# FOR_A-SOPRADOR.net
KiCad netlist of a schematic drawn in EAGLE
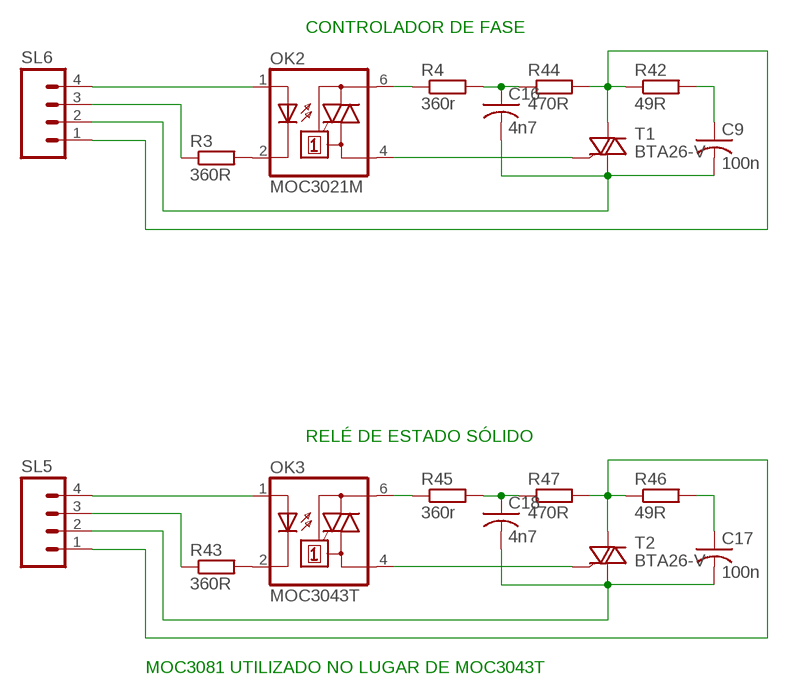
[diagram p0: schematic, sheet 1]

(export (version "E")
  (design (tool "Eeschema 10.0.6"))
  (components
    (comp (ref "C9")
      (value "100n")
      (footprint "eagle-import:C050-035X075")
      (libsource (lib "eagle-import") (part "C-US050-035X075"))
    )
    (comp (ref "C16")
      (value "4n7")
      (footprint "eagle-import:C050-035X075")
      (libsource (lib "eagle-import") (part "C-US050-035X075"))
    )
    (comp (ref "C17")
      (value "100n")
      (footprint "eagle-import:C050-035X075")
      (libsource (lib "eagle-import") (part "C-US050-035X075"))
    )
    (comp (ref "C18")
      (value "4n7")
      (footprint "eagle-import:C050-035X075")
      (libsource (lib "eagle-import") (part "C-US050-035X075"))
    )
    (comp (ref "OK2")
      (value "MOC3021M")
      (footprint "eagle-import:DIL06")
      (fields (field (name "MF") "FAIRCHILD SEMICONDUCTOR") (field (name "MPN") "MOC3021-M"))
      (libsource (lib "eagle-import") (part "MOC30M21"))
    )
    (comp (ref "OK3")
      (value "MOC3043T")
      (footprint "eagle-import:DIL06B")
      (fields (field (name "MF") "FAIRCHILD SEMICONDUCTOR") (field (name "MPN") "MOC3043TM"))
      (libsource (lib "eagle-import") (part "MOC30T43"))
    )
    (comp (ref "R3")
      (value "360R")
      (footprint "eagle-import:0207_10")
      (libsource (lib "eagle-import") (part "R-EU_0207/10"))
    )
    (comp (ref "R4")
      (value "360r")
      (footprint "eagle-import:0207_10")
      (libsource (lib "eagle-import") (part "R-EU_0207/10"))
    )
    (comp (ref "R42")
      (value "49R")
      (footprint "eagle-import:0207_10")
      (libsource (lib "eagle-import") (part "R-EU_0207/10"))
    )
    (comp (ref "R43")
      (value "360R")
      (footprint "eagle-import:0207_10")
      (libsource (lib "eagle-import") (part "R-EU_0207/10"))
    )
    (comp (ref "R44")
      (value "470R")
      (footprint "eagle-import:0309_12")
      (libsource (lib "eagle-import") (part "R-EU_0309/12"))
    )
    (comp (ref "R45")
      (value "360r")
      (footprint "eagle-import:0207_10")
      (libsource (lib "eagle-import") (part "R-EU_0207/10"))
    )
    (comp (ref "R46")
      (value "49R")
      (footprint "eagle-import:0207_10")
      (libsource (lib "eagle-import") (part "R-EU_0207/10"))
    )
    (comp (ref "R47")
      (value "470R")
      (footprint "eagle-import:0309_12")
      (libsource (lib "eagle-import") (part "R-EU_0309/12"))
    )
    (comp (ref "SL5")
      (value "M04")
      (footprint "eagle-import:04P")
      (libsource (lib "eagle-import") (part "M04"))
    )
    (comp (ref "SL6")
      (value "M04")
      (footprint "eagle-import:04P")
      (libsource (lib "eagle-import") (part "M04"))
    )
    (comp (ref "T1")
      (value "BTA26-V")
      (footprint "eagle-import:TOP3S-1")
      (libsource (lib "eagle-import") (part "BTA26-V"))
    )
    (comp (ref "T2")
      (value "BTA26-V")
      (footprint "eagle-import:TOP3S-1")
      (libsource (lib "eagle-import") (part "BTA26-V"))
    )
  )
  (nets
    (net (code "1") (name "Net-(C9-Pad1)") (class "Default")
      (node (ref "C9") (pin "1") (pinfunction "1_1") (pintype "passive"))
      (node (ref "R42") (pin "2") (pinfunction "2_2") (pintype "passive"))
    )
    (net (code "2") (name "Net-(C16-Pad1)") (class "Default")
      (node (ref "C16") (pin "1") (pinfunction "1_1") (pintype "passive"))
      (node (ref "R4") (pin "2") (pinfunction "2_2") (pintype "passive"))
      (node (ref "R44") (pin "1") (pinfunction "1_1") (pintype "passive"))
    )
    (net (code "3") (name "Net-(C16-Pad2)") (class "Default")
      (node (ref "C16") (pin "2") (pinfunction "2_2") (pintype "passive"))
      (node (ref "C9") (pin "2") (pinfunction "2_2") (pintype "passive"))
      (node (ref "SL6") (pin "2") (pinfunction "2_2") (pintype "passive"))
      (node (ref "T1") (pin "A1") (pinfunction "A1_A1") (pintype "passive"))
    )
    (net (code "4") (name "Net-(C17-Pad1)") (class "Default")
      (node (ref "C17") (pin "1") (pinfunction "1_1") (pintype "passive"))
      (node (ref "R46") (pin "2") (pinfunction "2_2") (pintype "passive"))
    )
    (net (code "5") (name "Net-(C17-Pad2)") (class "Default")
      (node (ref "C17") (pin "2") (pinfunction "2_2") (pintype "passive"))
      (node (ref "C18") (pin "2") (pinfunction "2_2") (pintype "passive"))
      (node (ref "SL5") (pin "2") (pinfunction "2_2") (pintype "passive"))
      (node (ref "T2") (pin "A1") (pinfunction "A1_A1") (pintype "passive"))
    )
    (net (code "6") (name "Net-(C18-Pad1)") (class "Default")
      (node (ref "C18") (pin "1") (pinfunction "1_1") (pintype "passive"))
      (node (ref "R45") (pin "2") (pinfunction "2_2") (pintype "passive"))
      (node (ref "R47") (pin "1") (pinfunction "1_1") (pintype "passive"))
    )
    (net (code "7") (name "Net-(OK2-A)") (class "Default")
      (node (ref "OK2") (pin "1") (pinfunction "A_1") (pintype "passive"))
      (node (ref "SL6") (pin "4") (pinfunction "4_4") (pintype "passive"))
    )
    (net (code "8") (name "Net-(OK2-A1)") (class "Default")
      (node (ref "OK2") (pin "4") (pinfunction "A1_4") (pintype "passive"))
      (node (ref "T1") (pin "G") (pinfunction "G_G") (pintype "passive"))
    )
    (net (code "9") (name "Net-(OK2-A2)") (class "Default")
      (node (ref "OK2") (pin "6") (pinfunction "A2_6") (pintype "passive"))
      (node (ref "R4") (pin "1") (pinfunction "1_1") (pintype "passive"))
    )
    (net (code "10") (name "Net-(OK2-C)") (class "Default")
      (node (ref "OK2") (pin "2") (pinfunction "C_2") (pintype "passive"))
      (node (ref "R3") (pin "2") (pinfunction "2_2") (pintype "passive"))
    )
    (net (code "11") (name "Net-(OK3-A)") (class "Default")
      (node (ref "OK3") (pin "1") (pinfunction "A_1") (pintype "passive"))
      (node (ref "SL5") (pin "4") (pinfunction "4_4") (pintype "passive"))
    )
    (net (code "12") (name "Net-(OK3-A1)") (class "Default")
      (node (ref "OK3") (pin "4") (pinfunction "A1_4") (pintype "passive"))
      (node (ref "T2") (pin "G") (pinfunction "G_G") (pintype "passive"))
    )
    (net (code "13") (name "Net-(OK3-A2)") (class "Default")
      (node (ref "OK3") (pin "6") (pinfunction "A2_6") (pintype "passive"))
      (node (ref "R45") (pin "1") (pinfunction "1_1") (pintype "passive"))
    )
    (net (code "14") (name "Net-(OK3-C)") (class "Default")
      (node (ref "OK3") (pin "2") (pinfunction "C_2") (pintype "passive"))
      (node (ref "R43") (pin "2") (pinfunction "2_2") (pintype "passive"))
    )
    (net (code "15") (name "Net-(R3-Pad1)") (class "Default")
      (node (ref "R3") (pin "1") (pinfunction "1_1") (pintype "passive"))
      (node (ref "SL6") (pin "3") (pinfunction "3_3") (pintype "passive"))
    )
    (net (code "16") (name "Net-(R42-Pad1)") (class "Default")
      (node (ref "R42") (pin "1") (pinfunction "1_1") (pintype "passive"))
      (node (ref "R44") (pin "2") (pinfunction "2_2") (pintype "passive"))
      (node (ref "SL6") (pin "1") (pinfunction "1_1") (pintype "passive"))
      (node (ref "T1") (pin "A2") (pinfunction "A2_A2") (pintype "passive"))
    )
    (net (code "17") (name "Net-(R43-Pad1)") (class "Default")
      (node (ref "R43") (pin "1") (pinfunction "1_1") (pintype "passive"))
      (node (ref "SL5") (pin "3") (pinfunction "3_3") (pintype "passive"))
    )
    (net (code "18") (name "Net-(R46-Pad1)") (class "Default")
      (node (ref "R46") (pin "1") (pinfunction "1_1") (pintype "passive"))
      (node (ref "R47") (pin "2") (pinfunction "2_2") (pintype "passive"))
      (node (ref "SL5") (pin "1") (pinfunction "1_1") (pintype "passive"))
      (node (ref "T2") (pin "A2") (pinfunction "A2_A2") (pintype "passive"))
    )
  )
)
